# Wireless.net
KiCad netlist of a schematic drawn in Altium Designer
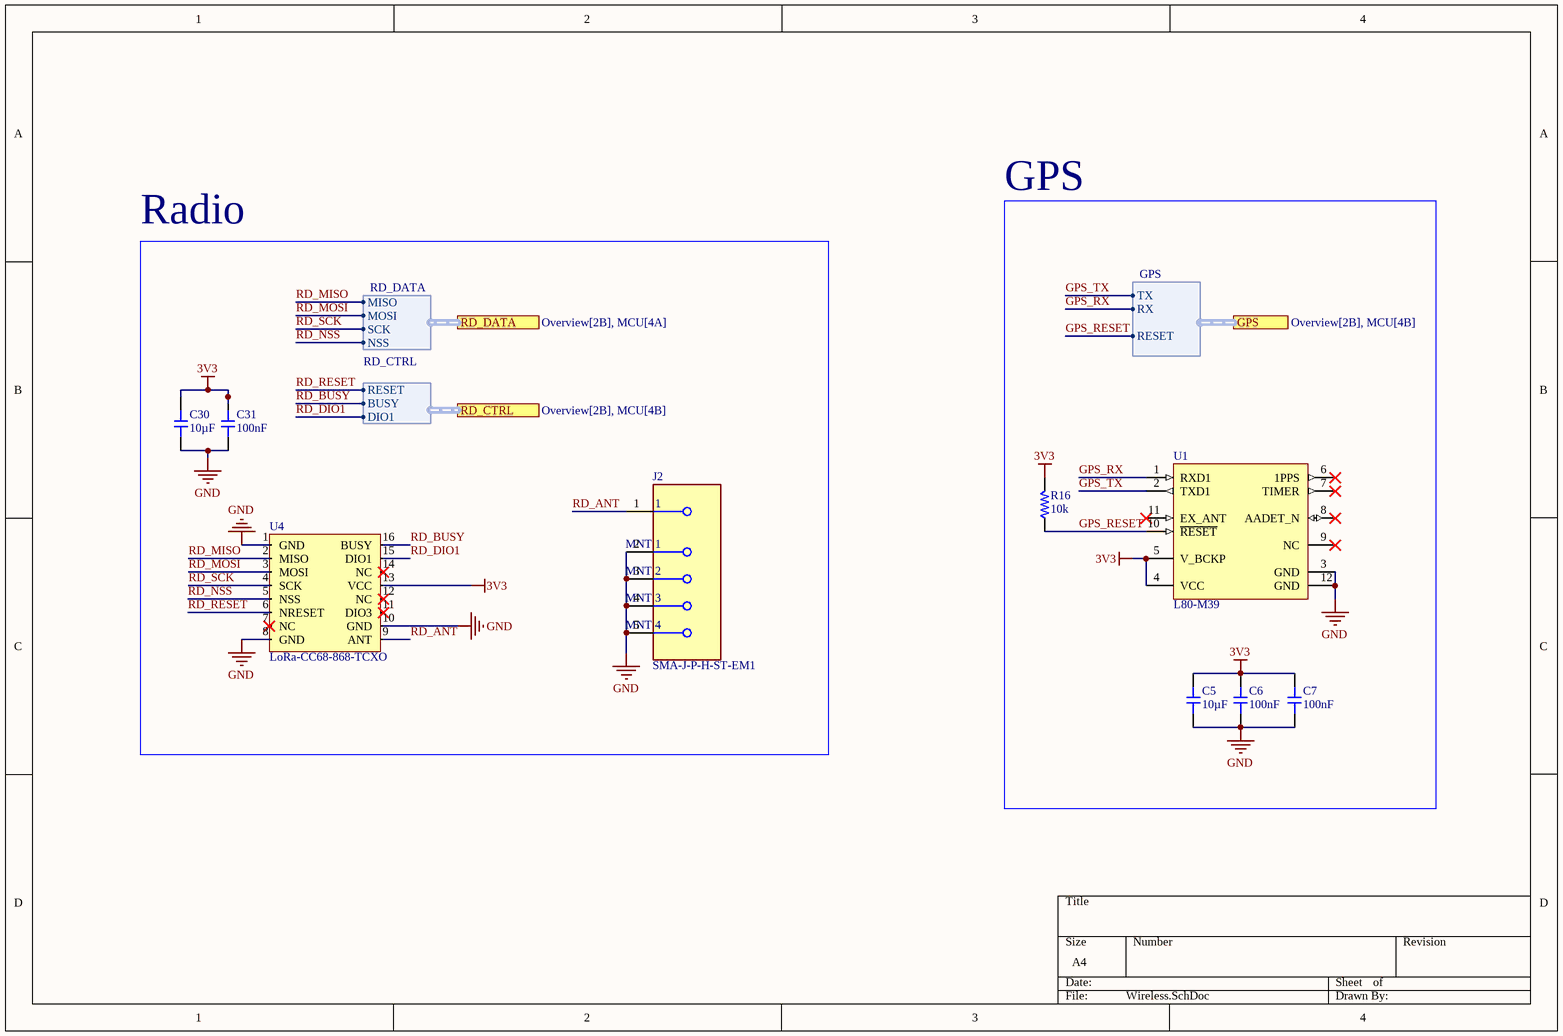
[diagram p0: Wireless.SchDoc]

(export (version "E")
  (design (tool "Eeschema 10.0.6"))
  (components
    (comp (ref "C5")
      (value "10µF")
      (footprint "CAP-0402")
      (description "Capacitor, Ceramic (MLCC), 10uF, ±20%, 6.3V, X5R, ±20%, SMD 0402")
      (fields (field (name "JLCPCB PART NUMBER") "C15525") (field (name "JLCPCB BASIC PART") "Yes"))
      (libsource (lib "StrathSEDS") (part "GRM21BR61H106KE43L"))
    )
    (comp (ref "C6")
      (value "100nF")
      (footprint "CAP-0402")
      (description "Capacitor, Ceramic (MLCC), 100nF, ±10%, 16V, X7R, ±10%, SMD 0402")
      (fields (field (name "TOLERANCE") "10%") (field (name "JLCPCB BASIC PART") "Yes"))
      (libsource (lib "StrathSEDS") (part "GRM21BR61H106KE43L"))
    )
    (comp (ref "C7")
      (value "100nF")
      (footprint "CAP-0402")
      (description "Capacitor, Ceramic (MLCC), 100nF, ±10%, 16V, X7R, ±10%, SMD 0402")
      (fields (field (name "TOLERANCE") "10%") (field (name "JLCPCB BASIC PART") "Yes"))
      (libsource (lib "StrathSEDS") (part "GRM21BR61H106KE43L"))
    )
    (comp (ref "C30")
      (value "10µF")
      (footprint "CAP-0402")
      (description "Capacitor, Ceramic (MLCC), 10uF, ±20%, 6.3V, X5R, ±20%, SMD 0402")
      (fields (field (name "JLCPCB PART NUMBER") "C15525") (field (name "JLCPCB BASIC PART") "Yes"))
      (libsource (lib "StrathSEDS") (part "GRM21BR61H106KE43L"))
    )
    (comp (ref "C31")
      (value "100nF")
      (footprint "CAP-0402")
      (description "Capacitor, Ceramic (MLCC), 100nF, ±10%, 16V, X7R, ±10%, SMD 0402")
      (fields (field (name "TOLERANCE") "10%") (field (name "JLCPCB BASIC PART") "Yes"))
      (libsource (lib "StrathSEDS") (part "GRM21BR61H106KE43L"))
    )
    (comp (ref "J2")
      (value "SMA-J-P-H-ST-EM1")
      (footprint "FP-SMA-J-P-H-ST-EM1-MFG")
      (description "RF SMA Connector, 1 Contact(s), Female, Board Mount, Surface Mount Terminal, Locking, Jack")
      (libsource (lib "StrathSEDS") (part "c65b8a639cdaef1819ea20b5466f8fa"))
    )
    (comp (ref "R16")
      (value "10k")
      (footprint "RES-0402")
      (description "Resistor, 10kΩ, ±1%, 62.5mW, 50V, ±100ppm/℃, -55℃~+155℃, SMD 0402")
      (fields (field (name "TOLERANCE") "1%") (field (name "JLCPCB PART NUMBER") "C25744"))
      (libsource (lib "StrathSEDS") (part "1206W4F7500T5E"))
    )
    (comp (ref "U1")
      (value "L80-M39")
      (footprint "QUEC-L80-M39-12_V")
      (description "GPS Module 15, 0x15, 0x4, 0mm SMD w/Antenna 3, 0V")
      (libsource (lib "StrathSEDS") (part "QUEC-L80-M39-12"))
    )
    (comp (ref "U4")
      (value "LoRa-CC68-868-TCXO")
      (footprint "LoRa-CC68-868-TCXO-Footprint-1")
      (description "LoRa-CC68 targeting 868MHz and with a TXCO")
      (libsource (lib "StrathSEDS") (part "LoRa-CC68-868-TCXO-Symbol-1"))
    )
  )
  (nets
    (net (code "4") (name "/GPS_RESET") (class "Default")
      (node (ref "R16") (pin "1") (pinfunction "1_1") (pintype "passive"))
      (node (ref "U1") (pin "10") (pinfunction "~{RESET}_10") (pintype "input"))
    )
    (net (code "5") (name "/GPS_RX") (class "Default")
      (node (ref "U1") (pin "1") (pinfunction "RXD1_1") (pintype "input"))
    )
    (net (code "6") (name "/GPS_TX") (class "Default")
      (node (ref "U1") (pin "2") (pinfunction "TXD1_2") (pintype "output"))
    )
    (net (code "7") (name "/RD_ANT") (class "Default")
      (node (ref "J2") (pin "1") (pinfunction "1_1") (pintype "passive"))
      (node (ref "U4") (pin "9") (pinfunction "ANT_9") (pintype "output"))
    )
    (net (code "8") (name "/RD_BUSY") (class "Default")
      (node (ref "U4") (pin "16") (pinfunction "BUSY_16") (pintype "output"))
    )
    (net (code "9") (name "/RD_DIO1") (class "Default")
      (node (ref "U4") (pin "15") (pinfunction "DIO1_15") (pintype "output"))
    )
    (net (code "10") (name "/RD_MISO") (class "Default")
      (node (ref "U4") (pin "2") (pinfunction "MISO_2") (pintype "output"))
    )
    (net (code "11") (name "/RD_MOSI") (class "Default")
      (node (ref "U4") (pin "3") (pinfunction "MOSI_3") (pintype "input"))
    )
    (net (code "12") (name "/RD_NSS") (class "Default")
      (node (ref "U4") (pin "5") (pinfunction "NSS_5") (pintype "input"))
    )
    (net (code "13") (name "/RD_RESET") (class "Default")
      (node (ref "U4") (pin "6") (pinfunction "NRESET_6") (pintype "input"))
    )
    (net (code "14") (name "/RD_SCK") (class "Default")
      (node (ref "U4") (pin "4") (pinfunction "SCK_4") (pintype "input"))
    )
    (net (code "18") (name "3V3") (class "Default")
      (node (ref "C30") (pin "2") (pinfunction "2_2") (pintype "passive"))
      (node (ref "C31") (pin "2") (pinfunction "2_2") (pintype "passive"))
      (node (ref "C5") (pin "2") (pinfunction "2_2") (pintype "passive"))
      (node (ref "C6") (pin "2") (pinfunction "2_2") (pintype "passive"))
      (node (ref "C7") (pin "2") (pinfunction "2_2") (pintype "passive"))
      (node (ref "R16") (pin "2") (pinfunction "2_2") (pintype "passive"))
      (node (ref "U1") (pin "4") (pinfunction "VCC_4") (pintype "power_in"))
      (node (ref "U1") (pin "5") (pinfunction "V_BCKP_5") (pintype "power_in"))
      (node (ref "U4") (pin "13") (pinfunction "VCC_13") (pintype "power_in"))
    )
    (net (code "19") (name "GND") (class "Default")
      (node (ref "C30") (pin "1") (pinfunction "1_1") (pintype "passive"))
      (node (ref "C31") (pin "1") (pinfunction "1_1") (pintype "passive"))
      (node (ref "C5") (pin "1") (pinfunction "1_1") (pintype "passive"))
      (node (ref "C6") (pin "1") (pinfunction "1_1") (pintype "passive"))
      (node (ref "C7") (pin "1") (pinfunction "1_1") (pintype "passive"))
      (node (ref "J2") (pin "2") (pinfunction "MNT_1_2") (pintype "passive"))
      (node (ref "J2") (pin "3") (pinfunction "MNT_2_3") (pintype "passive"))
      (node (ref "J2") (pin "4") (pinfunction "MNT_3_4") (pintype "passive"))
      (node (ref "J2") (pin "5") (pinfunction "MNT_4_5") (pintype "passive"))
      (node (ref "U1") (pin "12") (pinfunction "GND_12") (pintype "power_in"))
      (node (ref "U1") (pin "3") (pinfunction "GND_3") (pintype "power_in"))
      (node (ref "U4") (pin "1") (pinfunction "GND_1") (pintype "power_in"))
      (node (ref "U4") (pin "10") (pinfunction "GND_10") (pintype "input"))
      (node (ref "U4") (pin "8") (pinfunction "GND_8") (pintype "power_in"))
    )
    (net (code "20") (name "unconnected-(U1-1PPS-Pad6)") (class "Default")
      (node (ref "U1") (pin "6") (pinfunction "1PPS_6") (pintype "output+no_connect"))
    )
    (net (code "21") (name "unconnected-(U1-AADET_N-Pad8)") (class "Default")
      (node (ref "U1") (pin "8") (pinfunction "AADET_N_8") (pintype "bidirectional+no_connect"))
    )
    (net (code "22") (name "unconnected-(U1-EX_ANT-Pad11)") (class "Default")
      (node (ref "U1") (pin "11") (pinfunction "EX_ANT_11") (pintype "input+no_connect"))
    )
    (net (code "23") (name "unconnected-(U1-NC-Pad9)") (class "Default")
      (node (ref "U1") (pin "9") (pinfunction "NC_9") (pintype "passive+no_connect"))
    )
    (net (code "24") (name "unconnected-(U1-TIMER-Pad7)") (class "Default")
      (node (ref "U1") (pin "7") (pinfunction "TIMER_7") (pintype "output+no_connect"))
    )
    (net (code "25") (name "unconnected-(U4-DIO3-Pad11)") (class "Default")
      (node (ref "U4") (pin "11") (pinfunction "DIO3_11") (pintype "output+no_connect"))
    )
    (net (code "26") (name "unconnected-(U4-NC-Pad7)") (class "Default")
      (node (ref "U4") (pin "7") (pinfunction "NC_7") (pintype "passive+no_connect"))
    )
    (net (code "27") (name "unconnected-(U4-NC-Pad12)") (class "Default")
      (node (ref "U4") (pin "12") (pinfunction "NC_12") (pintype "passive+no_connect"))
    )
    (net (code "28") (name "unconnected-(U4-NC-Pad14)") (class "Default")
      (node (ref "U4") (pin "14") (pinfunction "NC_14") (pintype "passive+no_connect"))
    )
  )
)
